# VREG_RT9166-28PVL.net
KiCad netlist of a schematic drawn in Altium Designer
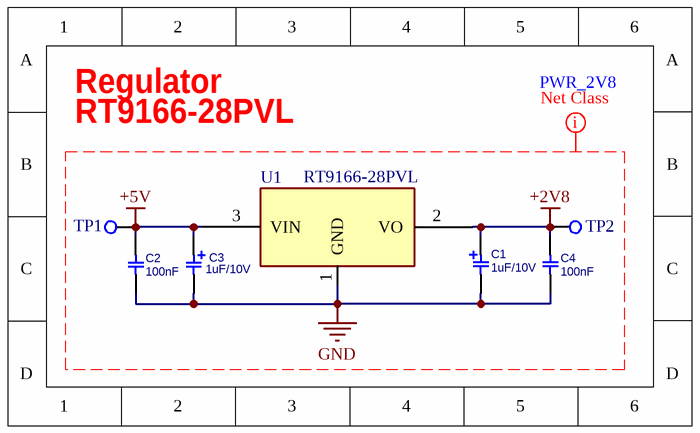
[diagram p0: VREG RT9166-28PVL.SchDoc]

(export (version "E")
  (design (tool "Eeschema 10.0.6"))
  (components
    (comp (ref "C1")
      (value "1uF/10V")
      (footprint "C_TN_3216")
      (description "CAP, SMD, TAN")
      (libsource (lib "Passive") (part "CAP_SMD_TAN"))
    )
    (comp (ref "C2")
      (value "100nF")
      (footprint "C0603S")
      (description "CAP, SMD, MLCC")
      (fields (field (name "MANF_P#") "MANF_PART#") (field (name "MANF") "Murata"))
      (libsource (lib "Passive") (part "CAP_SMD_MLCC"))
    )
    (comp (ref "C3")
      (value "1uF/10V")
      (footprint "C_TN_3216")
      (description "CAP, SMD, TAN")
      (libsource (lib "Passive") (part "CAP_SMD_TAN"))
    )
    (comp (ref "C4")
      (value "100nF")
      (footprint "C0603S")
      (description "CAP, SMD, MLCC")
      (fields (field (name "MANF_P#") "MANF_PART#") (field (name "MANF") "Murata"))
      (libsource (lib "Passive") (part "CAP_SMD_MLCC"))
    )
    (comp (ref "TP1")
      (value "Test Point")
      (footprint "TPSMD_C1")
      (libsource (lib "Passives") (part "Test Point"))
    )
    (comp (ref "TP2")
      (value "Test Point")
      (footprint "TPSMD_C1")
      (libsource (lib "Passives") (part "Test Point"))
    )
    (comp (ref "U1")
      (value "RT9166-28PVL")
      (footprint "SOT23_3")
      (description "REG, Linear, Fixed, 2.8v, 0.3A/0.6A, SOT23")
      (fields (field (name "MANF") "TI"))
      (libsource (lib "PW Components 97_481") (part "VREG_RT9166A-28PVL_SOT23"))
    )
  )
  (nets
    (net (code "1") (name "+2V8") (class "Default")
      (node (ref "C1") (pin "1") (pinfunction "1_1") (pintype "passive"))
      (node (ref "C4") (pin "1") (pinfunction "1_1") (pintype "passive"))
      (node (ref "TP2") (pin "1") (pinfunction "TP_1") (pintype "passive"))
      (node (ref "U1") (pin "2") (pinfunction "VO_2") (pintype "passive"))
    )
    (net (code "2") (name "+5V") (class "Default")
      (node (ref "C2") (pin "1") (pinfunction "1_1") (pintype "passive"))
      (node (ref "C3") (pin "1") (pinfunction "1_1") (pintype "passive"))
      (node (ref "TP1") (pin "1") (pinfunction "TP_1") (pintype "passive"))
      (node (ref "U1") (pin "3") (pinfunction "VIN_3") (pintype "passive"))
    )
    (net (code "3") (name "GND") (class "Default")
      (node (ref "C1") (pin "2") (pinfunction "2_2") (pintype "passive"))
      (node (ref "C2") (pin "2") (pinfunction "2_2") (pintype "passive"))
      (node (ref "C3") (pin "2") (pinfunction "2_2") (pintype "passive"))
      (node (ref "C4") (pin "2") (pinfunction "2_2") (pintype "passive"))
      (node (ref "U1") (pin "1") (pinfunction "GND_1") (pintype "passive"))
    )
  )
)
